# buffered_multiple.net
KiCad netlist of a schematic drawn in EAGLE
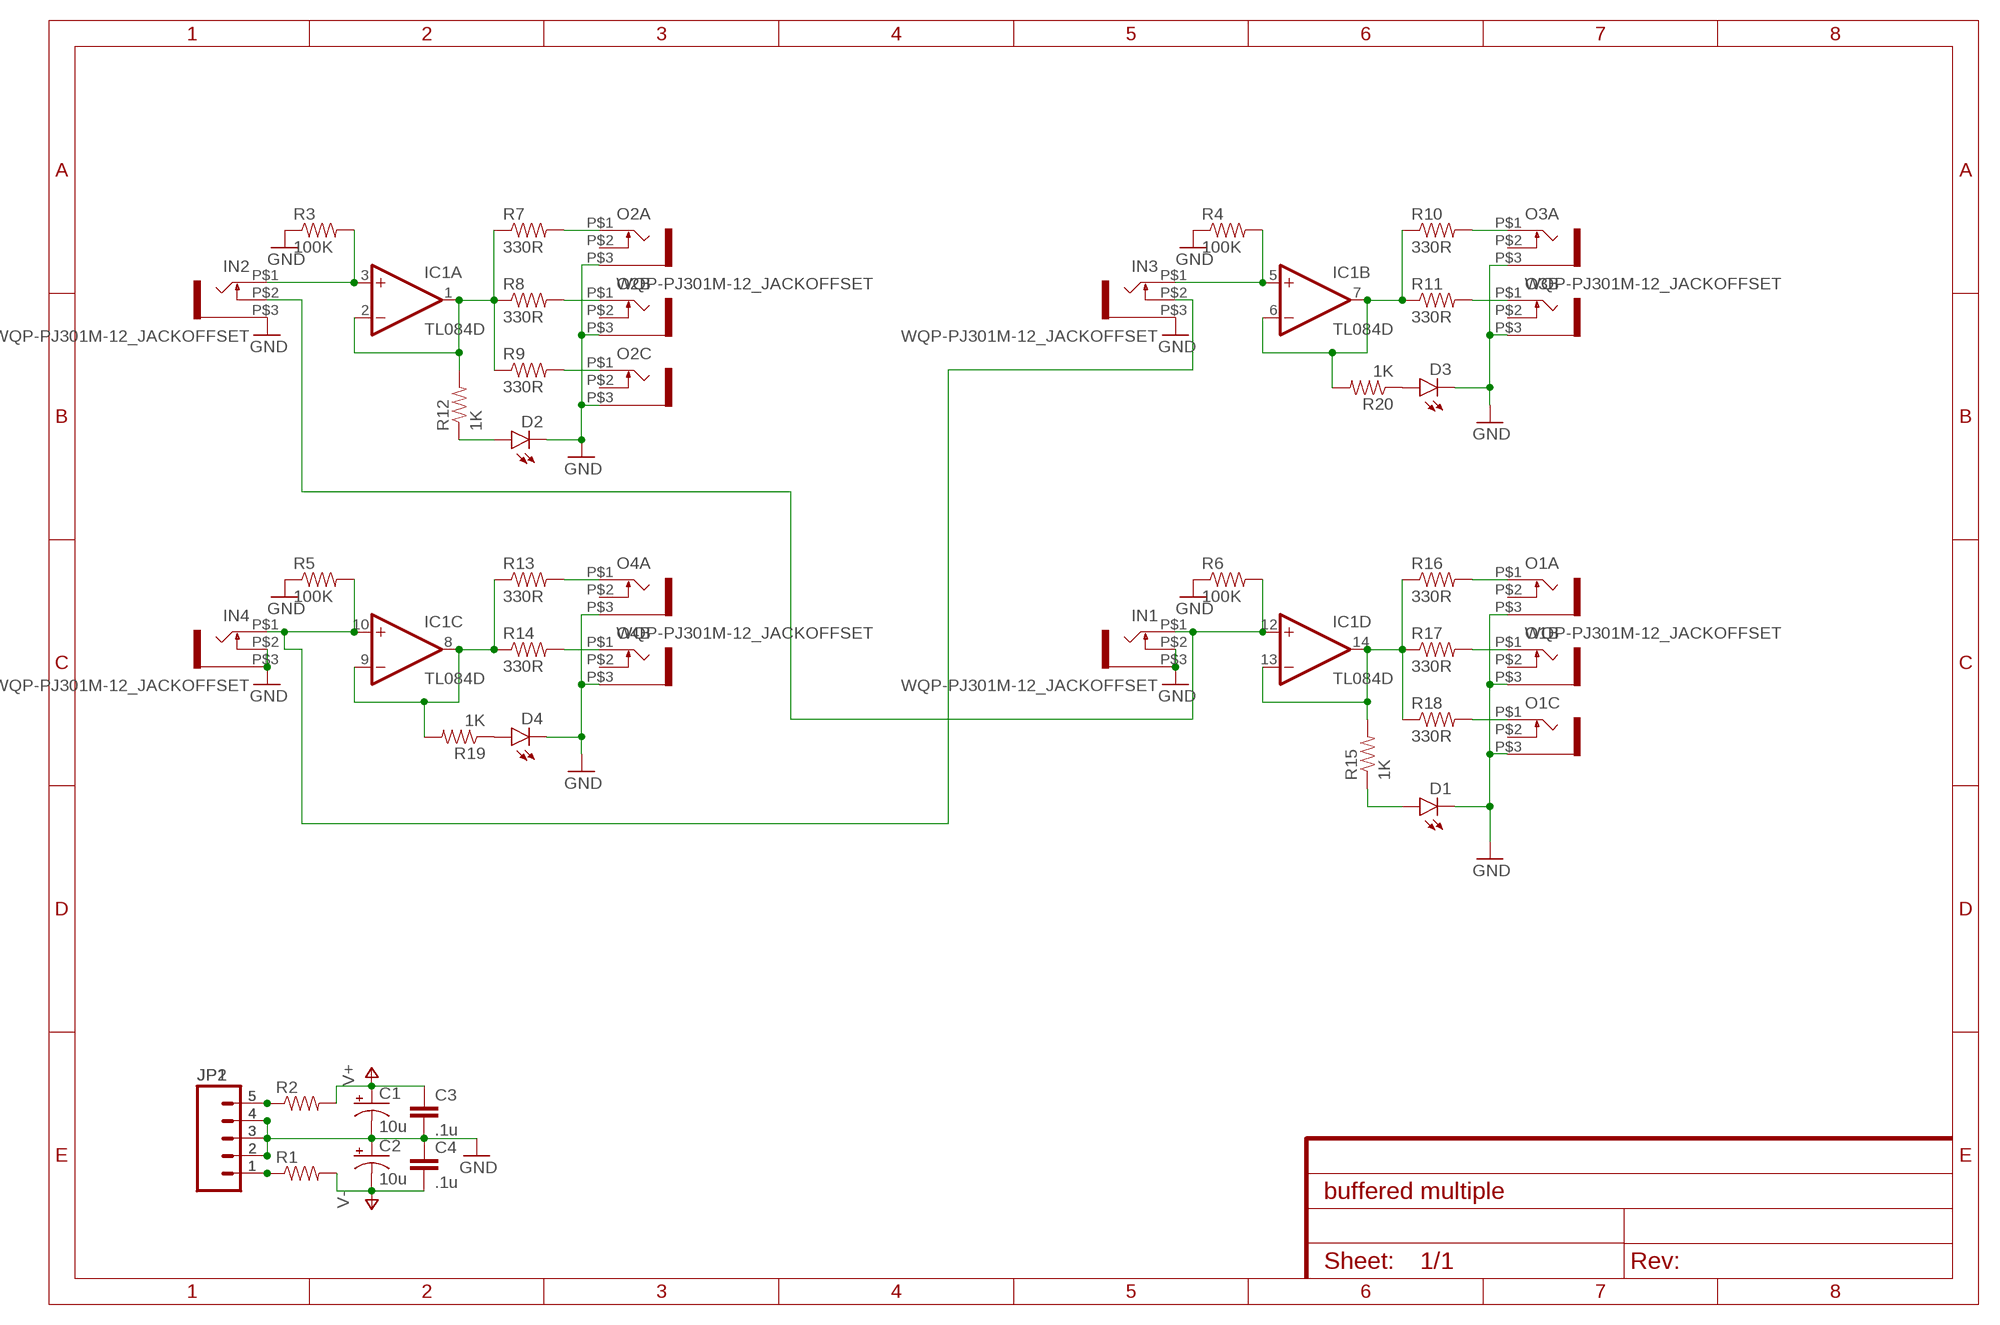
[diagram p0: schematic, sheet 1]

(export (version "E")
  (design (tool "Eeschema 10.0.6"))
  (components
    (comp (ref "C1")
      (value "10u")
      (footprint "eagle-import:EIA3216-KIT")
      (libsource (lib "eagle-import") (part "CAP_POL1206-KIT"))
    )
    (comp (ref "C2")
      (value "10u")
      (footprint "eagle-import:EIA3216-KIT")
      (libsource (lib "eagle-import") (part "CAP_POL1206-KIT"))
    )
    (comp (ref "C3")
      (value ".1u")
      (footprint "eagle-import:0805")
      (libsource (lib "eagle-import") (part "CAP0805"))
    )
    (comp (ref "C4")
      (value ".1u")
      (footprint "eagle-import:0805")
      (libsource (lib "eagle-import") (part "CAP0805"))
    )
    (comp (ref "D1")
      (value "LED3MM")
      (footprint "eagle-import:LED3MM")
      (libsource (lib "eagle-import") (part "LED3MM"))
    )
    (comp (ref "D2")
      (value "LED3MM")
      (footprint "eagle-import:LED3MM")
      (libsource (lib "eagle-import") (part "LED3MM"))
    )
    (comp (ref "D3")
      (value "LED3MM")
      (footprint "eagle-import:LED3MM")
      (libsource (lib "eagle-import") (part "LED3MM"))
    )
    (comp (ref "D4")
      (value "LED3MM")
      (footprint "eagle-import:LED3MM")
      (libsource (lib "eagle-import") (part "LED3MM"))
    )
    (comp (ref "IC1")
      (value "TL084D")
      (footprint "eagle-import:SO14")
      (libsource (lib "eagle-import") (part "TL084D"))
    )
    (comp (ref "IN1")
      (value "WQP-PJ301M-12_JACKOFFSET")
      (footprint "eagle-import:WQP-PJ301M-12_JACKOFFSET")
      (libsource (lib "eagle-import") (part "WQP-PJ301M-12_JACKOFFSET"))
    )
    (comp (ref "IN2")
      (value "WQP-PJ301M-12_JACKOFFSET")
      (footprint "eagle-import:WQP-PJ301M-12_JACKOFFSET")
      (libsource (lib "eagle-import") (part "WQP-PJ301M-12_JACKOFFSET"))
    )
    (comp (ref "IN3")
      (value "WQP-PJ301M-12_JACKOFFSET")
      (footprint "eagle-import:WQP-PJ301M-12_JACKOFFSET")
      (libsource (lib "eagle-import") (part "WQP-PJ301M-12_JACKOFFSET"))
    )
    (comp (ref "IN4")
      (value "WQP-PJ301M-12_JACKOFFSET")
      (footprint "eagle-import:WQP-PJ301M-12_JACKOFFSET")
      (libsource (lib "eagle-import") (part "WQP-PJ301M-12_JACKOFFSET"))
    )
    (comp (ref "JP1")
      (value "M05PTH")
      (footprint "eagle-import:1X05")
      (libsource (lib "eagle-import") (part "M05PTH"))
    )
    (comp (ref "JP2")
      (value "M05PTH")
      (footprint "eagle-import:1X05")
      (libsource (lib "eagle-import") (part "M05PTH"))
    )
    (comp (ref "O1A")
      (value "WQP-PJ301M-12_JACKOFFSET")
      (footprint "eagle-import:WQP-PJ301M-12_JACKOFFSET")
      (libsource (lib "eagle-import") (part "WQP-PJ301M-12_JACKOFFSET"))
    )
    (comp (ref "O1B")
      (value "WQP-PJ301M-12_JACK")
      (footprint "eagle-import:WQP-PJ301M-12_JACK")
      (libsource (lib "eagle-import") (part "WQP-PJ301M-12_JACK"))
    )
    (comp (ref "O1C")
      (value "WQP-PJ301M-12_JACK")
      (footprint "eagle-import:WQP-PJ301M-12_JACK")
      (libsource (lib "eagle-import") (part "WQP-PJ301M-12_JACK"))
    )
    (comp (ref "O2A")
      (value "WQP-PJ301M-12_JACKOFFSET")
      (footprint "eagle-import:WQP-PJ301M-12_JACKOFFSET")
      (libsource (lib "eagle-import") (part "WQP-PJ301M-12_JACKOFFSET"))
    )
    (comp (ref "O2B")
      (value "WQP-PJ301M-12_JACK")
      (footprint "eagle-import:WQP-PJ301M-12_JACK")
      (libsource (lib "eagle-import") (part "WQP-PJ301M-12_JACK"))
    )
    (comp (ref "O2C")
      (value "WQP-PJ301M-12_JACK")
      (footprint "eagle-import:WQP-PJ301M-12_JACK")
      (libsource (lib "eagle-import") (part "WQP-PJ301M-12_JACK"))
    )
    (comp (ref "O3A")
      (value "WQP-PJ301M-12_JACKOFFSET")
      (footprint "eagle-import:WQP-PJ301M-12_JACKOFFSET")
      (libsource (lib "eagle-import") (part "WQP-PJ301M-12_JACKOFFSET"))
    )
    (comp (ref "O3B")
      (value "WQP-PJ301M-12_JACK")
      (footprint "eagle-import:WQP-PJ301M-12_JACK")
      (libsource (lib "eagle-import") (part "WQP-PJ301M-12_JACK"))
    )
    (comp (ref "O4A")
      (value "WQP-PJ301M-12_JACKOFFSET")
      (footprint "eagle-import:WQP-PJ301M-12_JACKOFFSET")
      (libsource (lib "eagle-import") (part "WQP-PJ301M-12_JACKOFFSET"))
    )
    (comp (ref "O4B")
      (value "WQP-PJ301M-12_JACK")
      (footprint "eagle-import:WQP-PJ301M-12_JACK")
      (libsource (lib "eagle-import") (part "WQP-PJ301M-12_JACK"))
    )
    (comp (ref "R1")
      (value "RESISTOR0805-RES")
      (footprint "eagle-import:0805")
      (libsource (lib "eagle-import") (part "RESISTOR0805-RES"))
    )
    (comp (ref "R2")
      (value "RESISTOR0805-RES")
      (footprint "eagle-import:0805")
      (libsource (lib "eagle-import") (part "RESISTOR0805-RES"))
    )
    (comp (ref "R3")
      (value "100K")
      (footprint "eagle-import:0805")
      (libsource (lib "eagle-import") (part "RESISTOR0805-RES"))
    )
    (comp (ref "R4")
      (value "100K")
      (footprint "eagle-import:0805")
      (libsource (lib "eagle-import") (part "RESISTOR0805-RES"))
    )
    (comp (ref "R5")
      (value "100K")
      (footprint "eagle-import:0805")
      (libsource (lib "eagle-import") (part "RESISTOR0805-RES"))
    )
    (comp (ref "R6")
      (value "100K")
      (footprint "eagle-import:0805")
      (libsource (lib "eagle-import") (part "RESISTOR0805-RES"))
    )
    (comp (ref "R7")
      (value "330R")
      (footprint "eagle-import:0805")
      (libsource (lib "eagle-import") (part "RESISTOR0805-RES"))
    )
    (comp (ref "R8")
      (value "330R")
      (footprint "eagle-import:0805")
      (libsource (lib "eagle-import") (part "RESISTOR0805-RES"))
    )
    (comp (ref "R9")
      (value "330R")
      (footprint "eagle-import:0805")
      (libsource (lib "eagle-import") (part "RESISTOR0805-RES"))
    )
    (comp (ref "R10")
      (value "330R")
      (footprint "eagle-import:0805")
      (libsource (lib "eagle-import") (part "RESISTOR0805-RES"))
    )
    (comp (ref "R11")
      (value "330R")
      (footprint "eagle-import:0805")
      (libsource (lib "eagle-import") (part "RESISTOR0805-RES"))
    )
    (comp (ref "R12")
      (value "1K")
      (footprint "eagle-import:0805")
      (libsource (lib "eagle-import") (part "RESISTOR0805-RES"))
    )
    (comp (ref "R13")
      (value "330R")
      (footprint "eagle-import:0805")
      (libsource (lib "eagle-import") (part "RESISTOR0805-RES"))
    )
    (comp (ref "R14")
      (value "330R")
      (footprint "eagle-import:0805")
      (libsource (lib "eagle-import") (part "RESISTOR0805-RES"))
    )
    (comp (ref "R15")
      (value "1K")
      (footprint "eagle-import:0805")
      (libsource (lib "eagle-import") (part "RESISTOR0805-RES"))
    )
    (comp (ref "R16")
      (value "330R")
      (footprint "eagle-import:0805")
      (libsource (lib "eagle-import") (part "RESISTOR0805-RES"))
    )
    (comp (ref "R17")
      (value "330R")
      (footprint "eagle-import:0805")
      (libsource (lib "eagle-import") (part "RESISTOR0805-RES"))
    )
    (comp (ref "R18")
      (value "330R")
      (footprint "eagle-import:0805")
      (libsource (lib "eagle-import") (part "RESISTOR0805-RES"))
    )
    (comp (ref "R19")
      (value "1K")
      (footprint "eagle-import:0805")
      (libsource (lib "eagle-import") (part "RESISTOR0805-RES"))
    )
    (comp (ref "R20")
      (value "1K")
      (footprint "eagle-import:0805")
      (libsource (lib "eagle-import") (part "RESISTOR0805-RES"))
    )
  )
  (nets
    (net (code "1") (name "GND") (class "Default")
      (node (ref "C1") (pin "C") (pinfunction "-_C") (pintype "passive"))
      (node (ref "C2") (pin "A") (pinfunction "+_A") (pintype "passive"))
      (node (ref "C3") (pin "2") (pinfunction "2_2") (pintype "passive"))
      (node (ref "C4") (pin "1") (pinfunction "1_1") (pintype "passive"))
      (node (ref "D1") (pin "K") (pinfunction "C_K") (pintype "passive"))
      (node (ref "D2") (pin "K") (pinfunction "C_K") (pintype "passive"))
      (node (ref "D3") (pin "K") (pinfunction "C_K") (pintype "passive"))
      (node (ref "D4") (pin "K") (pinfunction "C_K") (pintype "passive"))
      (node (ref "IN1") (pin "P$2") (pinfunction "3_P$2") (pintype "passive"))
      (node (ref "IN1") (pin "P$3") (pinfunction "1_P$3") (pintype "passive"))
      (node (ref "IN2") (pin "P$3") (pinfunction "1_P$3") (pintype "passive"))
      (node (ref "IN3") (pin "P$3") (pinfunction "1_P$3") (pintype "passive"))
      (node (ref "IN4") (pin "P$2") (pinfunction "3_P$2") (pintype "passive"))
      (node (ref "IN4") (pin "P$3") (pinfunction "1_P$3") (pintype "passive"))
      (node (ref "JP1") (pin "2") (pinfunction "2_2") (pintype "passive"))
      (node (ref "JP1") (pin "3") (pinfunction "3_3") (pintype "passive"))
      (node (ref "JP1") (pin "4") (pinfunction "4_4") (pintype "passive"))
      (node (ref "JP2") (pin "2") (pinfunction "2_2") (pintype "passive"))
      (node (ref "JP2") (pin "3") (pinfunction "3_3") (pintype "passive"))
      (node (ref "JP2") (pin "4") (pinfunction "4_4") (pintype "passive"))
      (node (ref "O1A") (pin "P$3") (pinfunction "1_P$3") (pintype "passive"))
      (node (ref "O1B") (pin "P$3") (pinfunction "1_P$3") (pintype "passive"))
      (node (ref "O1C") (pin "P$3") (pinfunction "1_P$3") (pintype "passive"))
      (node (ref "O2A") (pin "P$3") (pinfunction "1_P$3") (pintype "passive"))
      (node (ref "O2B") (pin "P$3") (pinfunction "1_P$3") (pintype "passive"))
      (node (ref "O2C") (pin "P$3") (pinfunction "1_P$3") (pintype "passive"))
      (node (ref "O3A") (pin "P$3") (pinfunction "1_P$3") (pintype "passive"))
      (node (ref "O3B") (pin "P$3") (pinfunction "1_P$3") (pintype "passive"))
      (node (ref "O4A") (pin "P$3") (pinfunction "1_P$3") (pintype "passive"))
      (node (ref "O4B") (pin "P$3") (pinfunction "1_P$3") (pintype "passive"))
      (node (ref "R3") (pin "1") (pinfunction "1_1") (pintype "passive"))
      (node (ref "R4") (pin "1") (pinfunction "1_1") (pintype "passive"))
      (node (ref "R5") (pin "1") (pinfunction "1_1") (pintype "passive"))
      (node (ref "R6") (pin "1") (pinfunction "1_1") (pintype "passive"))
    )
    (net (code "2") (name "Net-(D1-PadA)") (class "Default")
      (node (ref "D1") (pin "A") (pinfunction "A_A") (pintype "passive"))
      (node (ref "R15") (pin "1") (pinfunction "1_1") (pintype "passive"))
    )
    (net (code "3") (name "Net-(D2-PadA)") (class "Default")
      (node (ref "D2") (pin "A") (pinfunction "A_A") (pintype "passive"))
      (node (ref "R12") (pin "1") (pinfunction "1_1") (pintype "passive"))
    )
    (net (code "4") (name "Net-(D3-PadA)") (class "Default")
      (node (ref "D3") (pin "A") (pinfunction "A_A") (pintype "passive"))
      (node (ref "R20") (pin "1") (pinfunction "1_1") (pintype "passive"))
    )
    (net (code "5") (name "Net-(D4-PadA)") (class "Default")
      (node (ref "D4") (pin "A") (pinfunction "A_A") (pintype "passive"))
      (node (ref "R19") (pin "1") (pinfunction "1_1") (pintype "passive"))
    )
    (net (code "6") (name "Net-(IC1A-+IN)") (class "Default")
      (node (ref "IC1") (pin "3") (pinfunction "+IN_3") (pintype "input"))
      (node (ref "IN2") (pin "P$1") (pinfunction "2_P$1") (pintype "passive"))
      (node (ref "R3") (pin "2") (pinfunction "2_2") (pintype "passive"))
    )
    (net (code "7") (name "Net-(IC1A--IN)") (class "Default")
      (node (ref "IC1") (pin "1") (pinfunction "OUT_1") (pintype "output"))
      (node (ref "IC1") (pin "2") (pinfunction "-IN_2") (pintype "input"))
      (node (ref "R12") (pin "2") (pinfunction "2_2") (pintype "passive"))
      (node (ref "R7") (pin "1") (pinfunction "1_1") (pintype "passive"))
      (node (ref "R8") (pin "1") (pinfunction "1_1") (pintype "passive"))
      (node (ref "R9") (pin "1") (pinfunction "1_1") (pintype "passive"))
    )
    (net (code "8") (name "Net-(IC1B-+IN)") (class "Default")
      (node (ref "IC1") (pin "5") (pinfunction "+IN_5") (pintype "input"))
      (node (ref "IN3") (pin "P$1") (pinfunction "2_P$1") (pintype "passive"))
      (node (ref "R4") (pin "2") (pinfunction "2_2") (pintype "passive"))
    )
    (net (code "9") (name "Net-(IC1B--IN)") (class "Default")
      (node (ref "IC1") (pin "6") (pinfunction "-IN_6") (pintype "input"))
      (node (ref "IC1") (pin "7") (pinfunction "OUT_7") (pintype "output"))
      (node (ref "R10") (pin "1") (pinfunction "1_1") (pintype "passive"))
      (node (ref "R11") (pin "1") (pinfunction "1_1") (pintype "passive"))
      (node (ref "R20") (pin "2") (pinfunction "2_2") (pintype "passive"))
    )
    (net (code "10") (name "Net-(IC1C-+IN)") (class "Default")
      (node (ref "IC1") (pin "10") (pinfunction "+IN_10") (pintype "input"))
      (node (ref "IN3") (pin "P$2") (pinfunction "3_P$2") (pintype "passive"))
      (node (ref "IN4") (pin "P$1") (pinfunction "2_P$1") (pintype "passive"))
      (node (ref "R5") (pin "2") (pinfunction "2_2") (pintype "passive"))
    )
    (net (code "11") (name "Net-(IC1C--IN)") (class "Default")
      (node (ref "IC1") (pin "8") (pinfunction "OUT_8") (pintype "output"))
      (node (ref "IC1") (pin "9") (pinfunction "-IN_9") (pintype "input"))
      (node (ref "R13") (pin "1") (pinfunction "1_1") (pintype "passive"))
      (node (ref "R14") (pin "1") (pinfunction "1_1") (pintype "passive"))
      (node (ref "R19") (pin "2") (pinfunction "2_2") (pintype "passive"))
    )
    (net (code "12") (name "Net-(IC1D-+IN)") (class "Default")
      (node (ref "IC1") (pin "12") (pinfunction "+IN_12") (pintype "input"))
      (node (ref "IN1") (pin "P$1") (pinfunction "2_P$1") (pintype "passive"))
      (node (ref "IN2") (pin "P$2") (pinfunction "3_P$2") (pintype "passive"))
      (node (ref "R6") (pin "2") (pinfunction "2_2") (pintype "passive"))
    )
    (net (code "13") (name "Net-(IC1D--IN)") (class "Default")
      (node (ref "IC1") (pin "13") (pinfunction "-IN_13") (pintype "input"))
      (node (ref "IC1") (pin "14") (pinfunction "OUT_14") (pintype "output"))
      (node (ref "R15") (pin "2") (pinfunction "2_2") (pintype "passive"))
      (node (ref "R16") (pin "1") (pinfunction "1_1") (pintype "passive"))
      (node (ref "R17") (pin "1") (pinfunction "1_1") (pintype "passive"))
      (node (ref "R18") (pin "1") (pinfunction "1_1") (pintype "passive"))
    )
    (net (code "14") (name "Net-(JP1-Pad1)") (class "Default")
      (node (ref "JP1") (pin "1") (pinfunction "1_1") (pintype "passive"))
      (node (ref "JP2") (pin "1") (pinfunction "1_1") (pintype "passive"))
      (node (ref "R1") (pin "1") (pinfunction "1_1") (pintype "passive"))
    )
    (net (code "15") (name "Net-(JP1-Pad5)") (class "Default")
      (node (ref "JP1") (pin "5") (pinfunction "5_5") (pintype "passive"))
      (node (ref "JP2") (pin "5") (pinfunction "5_5") (pintype "passive"))
      (node (ref "R2") (pin "1") (pinfunction "1_1") (pintype "passive"))
    )
    (net (code "16") (name "Net-(O1A-2)") (class "Default")
      (node (ref "O1A") (pin "P$1") (pinfunction "2_P$1") (pintype "passive"))
      (node (ref "R16") (pin "2") (pinfunction "2_2") (pintype "passive"))
    )
    (net (code "17") (name "Net-(O1B-2)") (class "Default")
      (node (ref "O1B") (pin "P$1") (pinfunction "2_P$1") (pintype "passive"))
      (node (ref "R17") (pin "2") (pinfunction "2_2") (pintype "passive"))
    )
    (net (code "18") (name "Net-(O1C-2)") (class "Default")
      (node (ref "O1C") (pin "P$1") (pinfunction "2_P$1") (pintype "passive"))
      (node (ref "R18") (pin "2") (pinfunction "2_2") (pintype "passive"))
    )
    (net (code "19") (name "Net-(O2A-2)") (class "Default")
      (node (ref "O2A") (pin "P$1") (pinfunction "2_P$1") (pintype "passive"))
      (node (ref "R7") (pin "2") (pinfunction "2_2") (pintype "passive"))
    )
    (net (code "20") (name "Net-(O2B-2)") (class "Default")
      (node (ref "O2B") (pin "P$1") (pinfunction "2_P$1") (pintype "passive"))
      (node (ref "R8") (pin "2") (pinfunction "2_2") (pintype "passive"))
    )
    (net (code "21") (name "Net-(O2C-2)") (class "Default")
      (node (ref "O2C") (pin "P$1") (pinfunction "2_P$1") (pintype "passive"))
      (node (ref "R9") (pin "2") (pinfunction "2_2") (pintype "passive"))
    )
    (net (code "22") (name "Net-(O3A-2)") (class "Default")
      (node (ref "O3A") (pin "P$1") (pinfunction "2_P$1") (pintype "passive"))
      (node (ref "R10") (pin "2") (pinfunction "2_2") (pintype "passive"))
    )
    (net (code "23") (name "Net-(O3B-2)") (class "Default")
      (node (ref "O3B") (pin "P$1") (pinfunction "2_P$1") (pintype "passive"))
      (node (ref "R11") (pin "2") (pinfunction "2_2") (pintype "passive"))
    )
    (net (code "24") (name "Net-(O4A-2)") (class "Default")
      (node (ref "O4A") (pin "P$1") (pinfunction "2_P$1") (pintype "passive"))
      (node (ref "R13") (pin "2") (pinfunction "2_2") (pintype "passive"))
    )
    (net (code "25") (name "Net-(O4B-2)") (class "Default")
      (node (ref "O4B") (pin "P$1") (pinfunction "2_P$1") (pintype "passive"))
      (node (ref "R14") (pin "2") (pinfunction "2_2") (pintype "passive"))
    )
    (net (code "26") (name "V+") (class "Default")
      (node (ref "C1") (pin "A") (pinfunction "+_A") (pintype "passive"))
      (node (ref "C3") (pin "1") (pinfunction "1_1") (pintype "passive"))
      (node (ref "R2") (pin "2") (pinfunction "2_2") (pintype "passive"))
    )
    (net (code "27") (name "V-") (class "Default")
      (node (ref "C2") (pin "C") (pinfunction "-_C") (pintype "passive"))
      (node (ref "C4") (pin "2") (pinfunction "2_2") (pintype "passive"))
      (node (ref "R1") (pin "2") (pinfunction "2_2") (pintype "passive"))
    )
    (net (code "28") (name "unconnected-(O1A-3-PadP$2)") (class "Default")
      (node (ref "O1A") (pin "P$2") (pinfunction "3_P$2") (pintype "passive"))
    )
    (net (code "29") (name "unconnected-(O1B-3-PadP$2)") (class "Default")
      (node (ref "O1B") (pin "P$2") (pinfunction "3_P$2") (pintype "passive"))
    )
    (net (code "30") (name "unconnected-(O1C-3-PadP$2)") (class "Default")
      (node (ref "O1C") (pin "P$2") (pinfunction "3_P$2") (pintype "passive"))
    )
    (net (code "31") (name "unconnected-(O2A-3-PadP$2)") (class "Default")
      (node (ref "O2A") (pin "P$2") (pinfunction "3_P$2") (pintype "passive"))
    )
    (net (code "32") (name "unconnected-(O2B-3-PadP$2)") (class "Default")
      (node (ref "O2B") (pin "P$2") (pinfunction "3_P$2") (pintype "passive"))
    )
    (net (code "33") (name "unconnected-(O2C-3-PadP$2)") (class "Default")
      (node (ref "O2C") (pin "P$2") (pinfunction "3_P$2") (pintype "passive"))
    )
    (net (code "34") (name "unconnected-(O3A-3-PadP$2)") (class "Default")
      (node (ref "O3A") (pin "P$2") (pinfunction "3_P$2") (pintype "passive"))
    )
    (net (code "35") (name "unconnected-(O3B-3-PadP$2)") (class "Default")
      (node (ref "O3B") (pin "P$2") (pinfunction "3_P$2") (pintype "passive"))
    )
    (net (code "36") (name "unconnected-(O4A-3-PadP$2)") (class "Default")
      (node (ref "O4A") (pin "P$2") (pinfunction "3_P$2") (pintype "passive"))
    )
    (net (code "37") (name "unconnected-(O4B-3-PadP$2)") (class "Default")
      (node (ref "O4B") (pin "P$2") (pinfunction "3_P$2") (pintype "passive"))
    )
  )
)
